# TRS_breakout.net
KiCad netlist of a schematic drawn in EAGLE
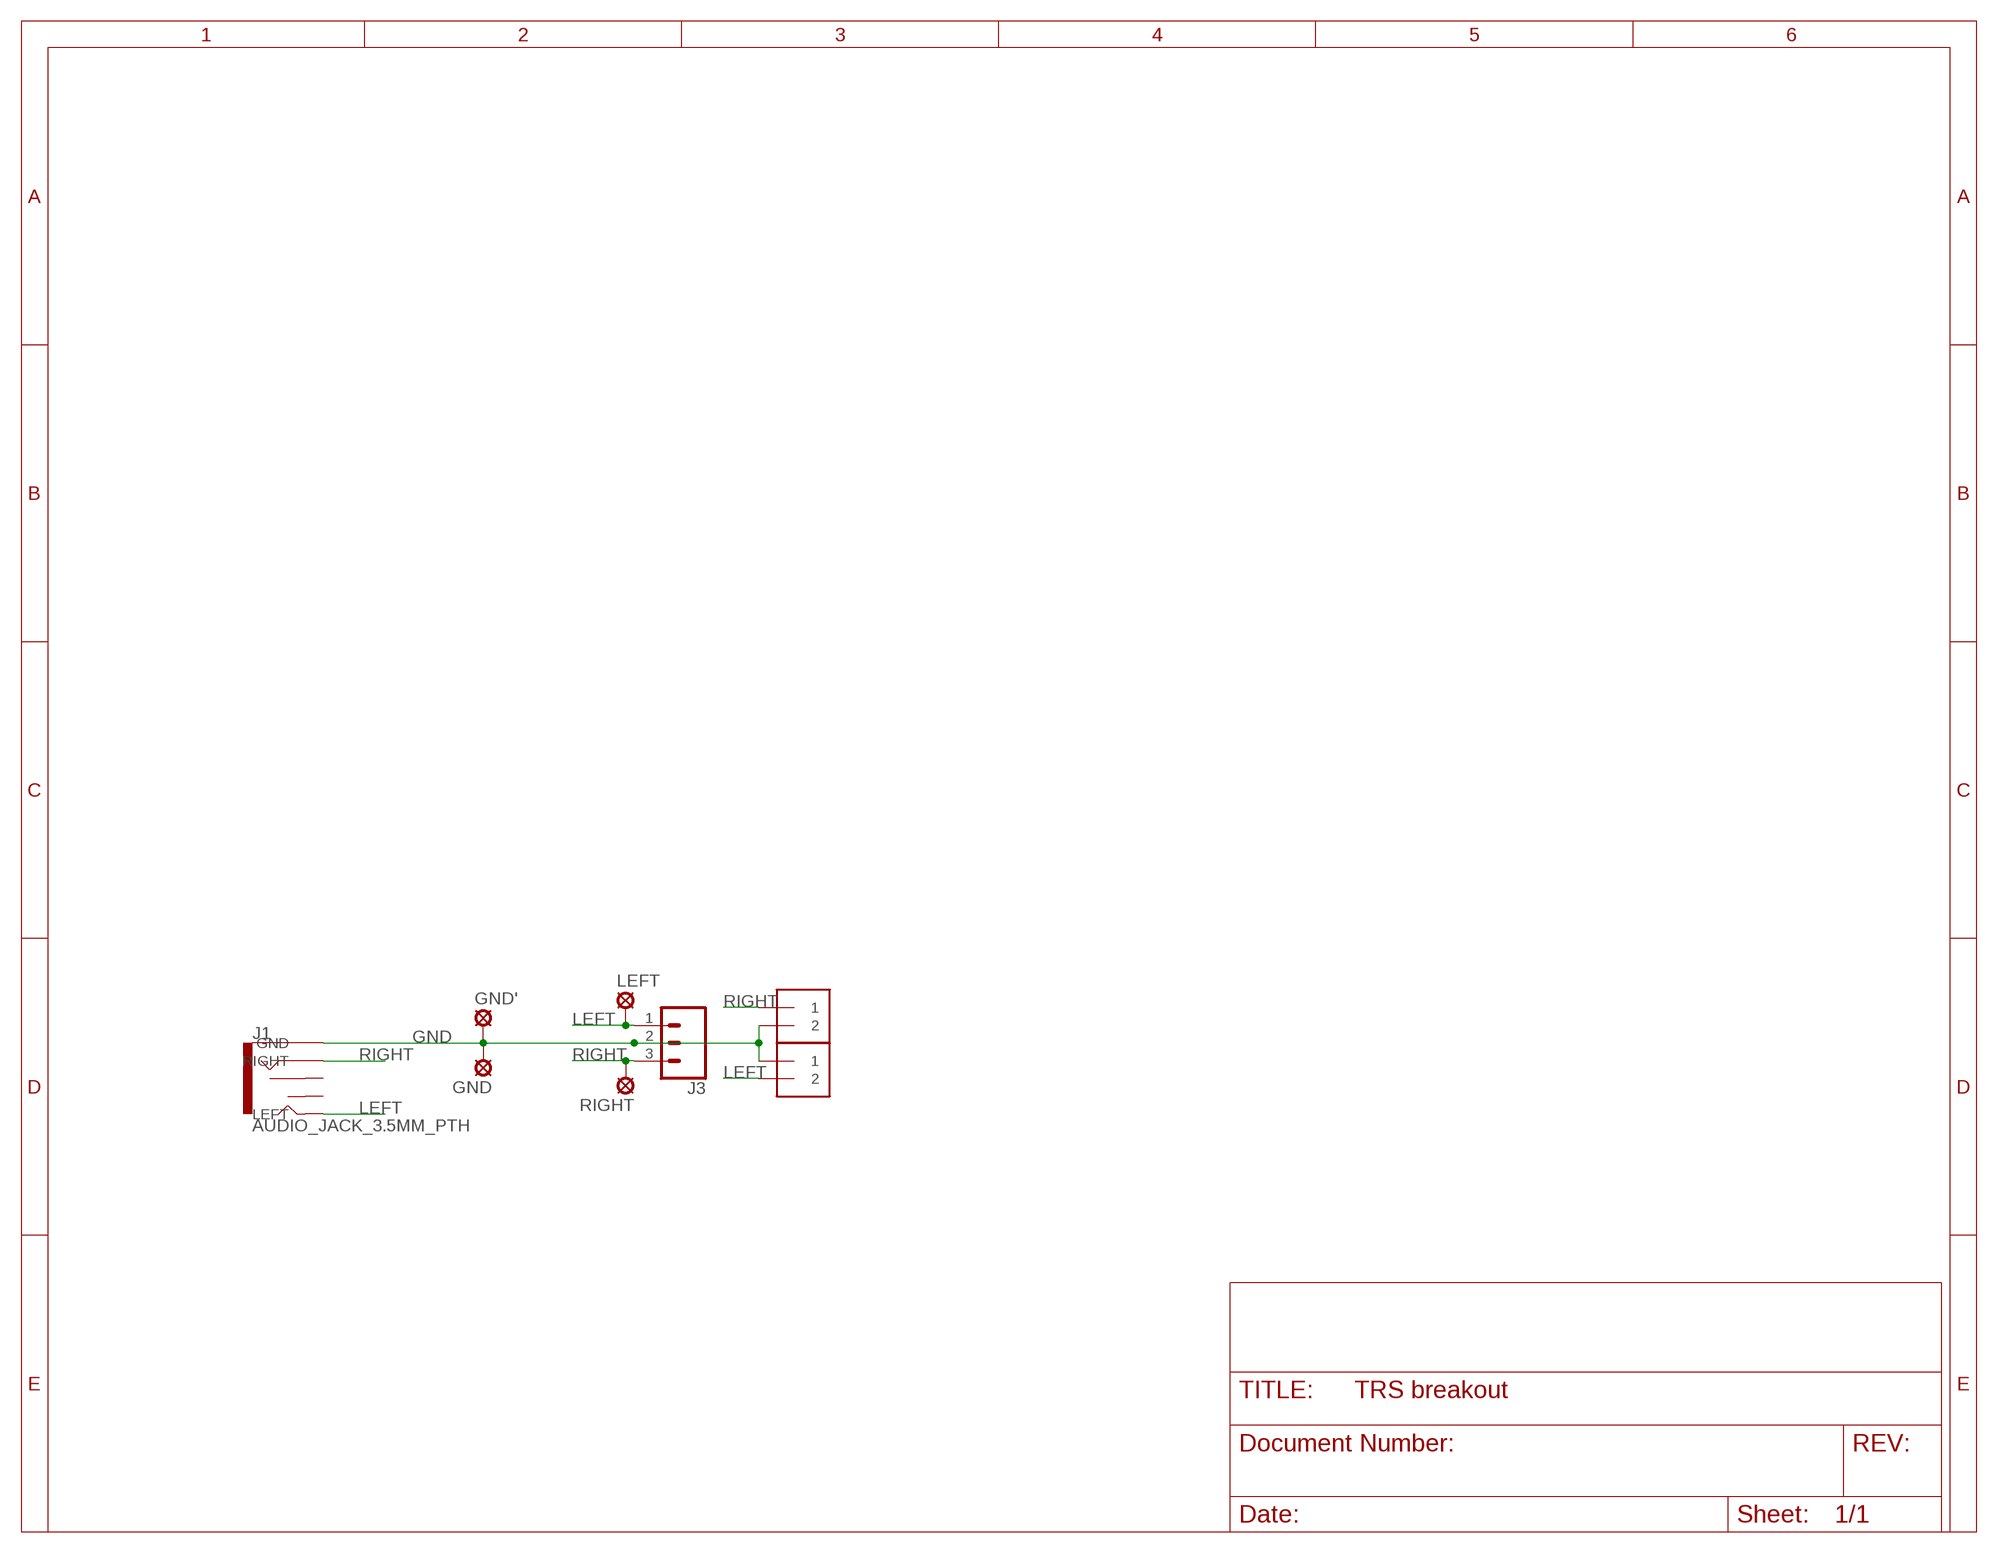
[diagram p0: schematic, sheet 1]

(export (version "E")
  (design (tool "Eeschema 10.0.6"))
  (components
    (comp (ref "GND")
      (value "SE14")
      (footprint "eagle-import:SE14")
      (libsource (lib "eagle-import") (part "SE14"))
    )
    (comp (ref "GND'")
      (value "SE14")
      (footprint "eagle-import:SE14")
      (libsource (lib "eagle-import") (part "SE14"))
    )
    (comp (ref "J1")
      (value "AUDIO_JACK_3.5MM_PTH")
      (footprint "eagle-import:AUDIO-JACK")
      (libsource (lib "eagle-import") (part "AUDIO_JACK_3.5MM_PTH"))
    )
    (comp (ref "J3")
      (value "CONN_03LOCK_LONGPADS")
      (footprint "eagle-import:1X03_LOCK_LONGPADS")
      (libsource (lib "eagle-import") (part "CONN_03LOCK_LONGPADS"))
    )
    (comp (ref "J4")
      (value "1X2-3.5MM")
      (footprint "eagle-import:1X2-3.5MM")
      (libsource (lib "eagle-import") (part "1X2-3.5MM"))
    )
    (comp (ref "J5")
      (value "1X2-3.5MM")
      (footprint "eagle-import:1X2-3.5MM")
      (libsource (lib "eagle-import") (part "1X2-3.5MM"))
    )
    (comp (ref "LEFT")
      (value "SE14")
      (footprint "eagle-import:SE14")
      (libsource (lib "eagle-import") (part "SE14"))
    )
    (comp (ref "RIGHT")
      (value "SE14")
      (footprint "eagle-import:SE14")
      (libsource (lib "eagle-import") (part "SE14"))
    )
  )
  (nets
    (net (code "1") (name "/GND") (class "Default")
      (node (ref "GND") (pin "MP") (pinfunction "MP_MP") (pintype "passive"))
      (node (ref "GND'") (pin "MP") (pinfunction "MP_MP") (pintype "passive"))
      (node (ref "J1") (pin "GND") (pinfunction "GND_GND") (pintype "bidirectional"))
      (node (ref "J3") (pin "2") (pinfunction "2_2") (pintype "passive"))
      (node (ref "J4") (pin "1") (pinfunction "1_1") (pintype "passive"))
      (node (ref "J5") (pin "2") (pinfunction "2_2") (pintype "passive"))
    )
    (net (code "2") (name "/LEFT") (class "Default")
      (node (ref "J1") (pin "LEFT") (pinfunction "LEFT_LEFT") (pintype "bidirectional"))
      (node (ref "J3") (pin "1") (pinfunction "1_1") (pintype "passive"))
      (node (ref "J4") (pin "2") (pinfunction "2_2") (pintype "passive"))
      (node (ref "LEFT") (pin "MP") (pinfunction "MP_MP") (pintype "passive"))
    )
    (net (code "3") (name "/RIGHT") (class "Default")
      (node (ref "J1") (pin "RIGHT") (pinfunction "RIGHT_RIGHT") (pintype "bidirectional"))
      (node (ref "J3") (pin "3") (pinfunction "3_3") (pintype "passive"))
      (node (ref "J5") (pin "1") (pinfunction "1_1") (pintype "passive"))
      (node (ref "RIGHT") (pin "MP") (pinfunction "MP_MP") (pintype "passive"))
    )
    (net (code "4") (name "unconnected-(J1-PadRSH)") (class "Default")
      (node (ref "J1") (pin "RSH") (pinfunction "RSH_RSH") (pintype "bidirectional"))
    )
    (net (code "5") (name "unconnected-(J1-PadTSH)") (class "Default")
      (node (ref "J1") (pin "TSH") (pinfunction "TSH_TSH") (pintype "bidirectional"))
    )
  )
)
